# falownik.net
KiCad netlist of a schematic drawn in EAGLE
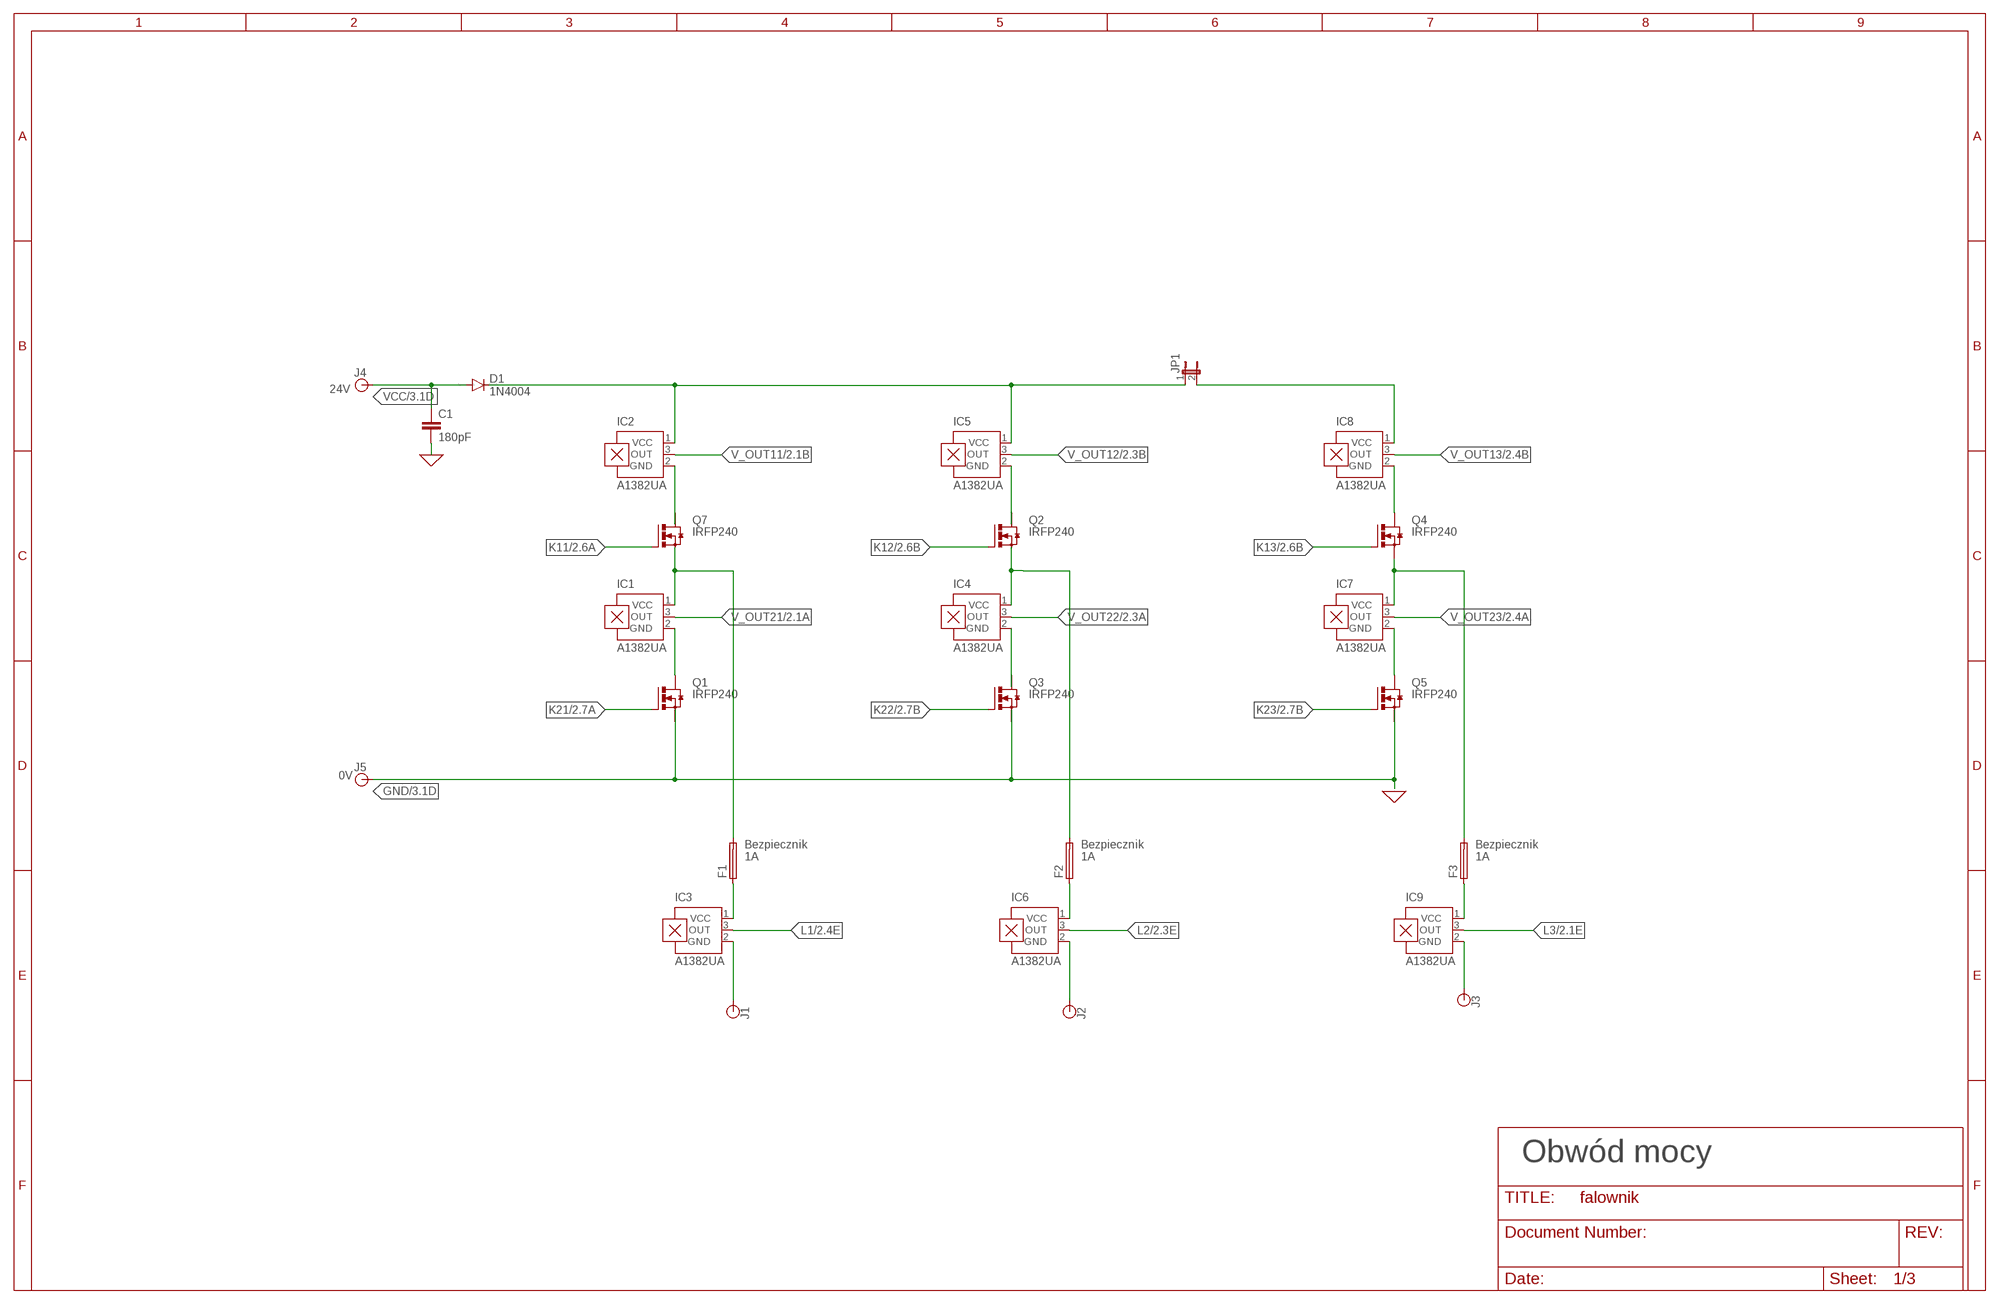
[diagram p0: schematic, sheet 1]
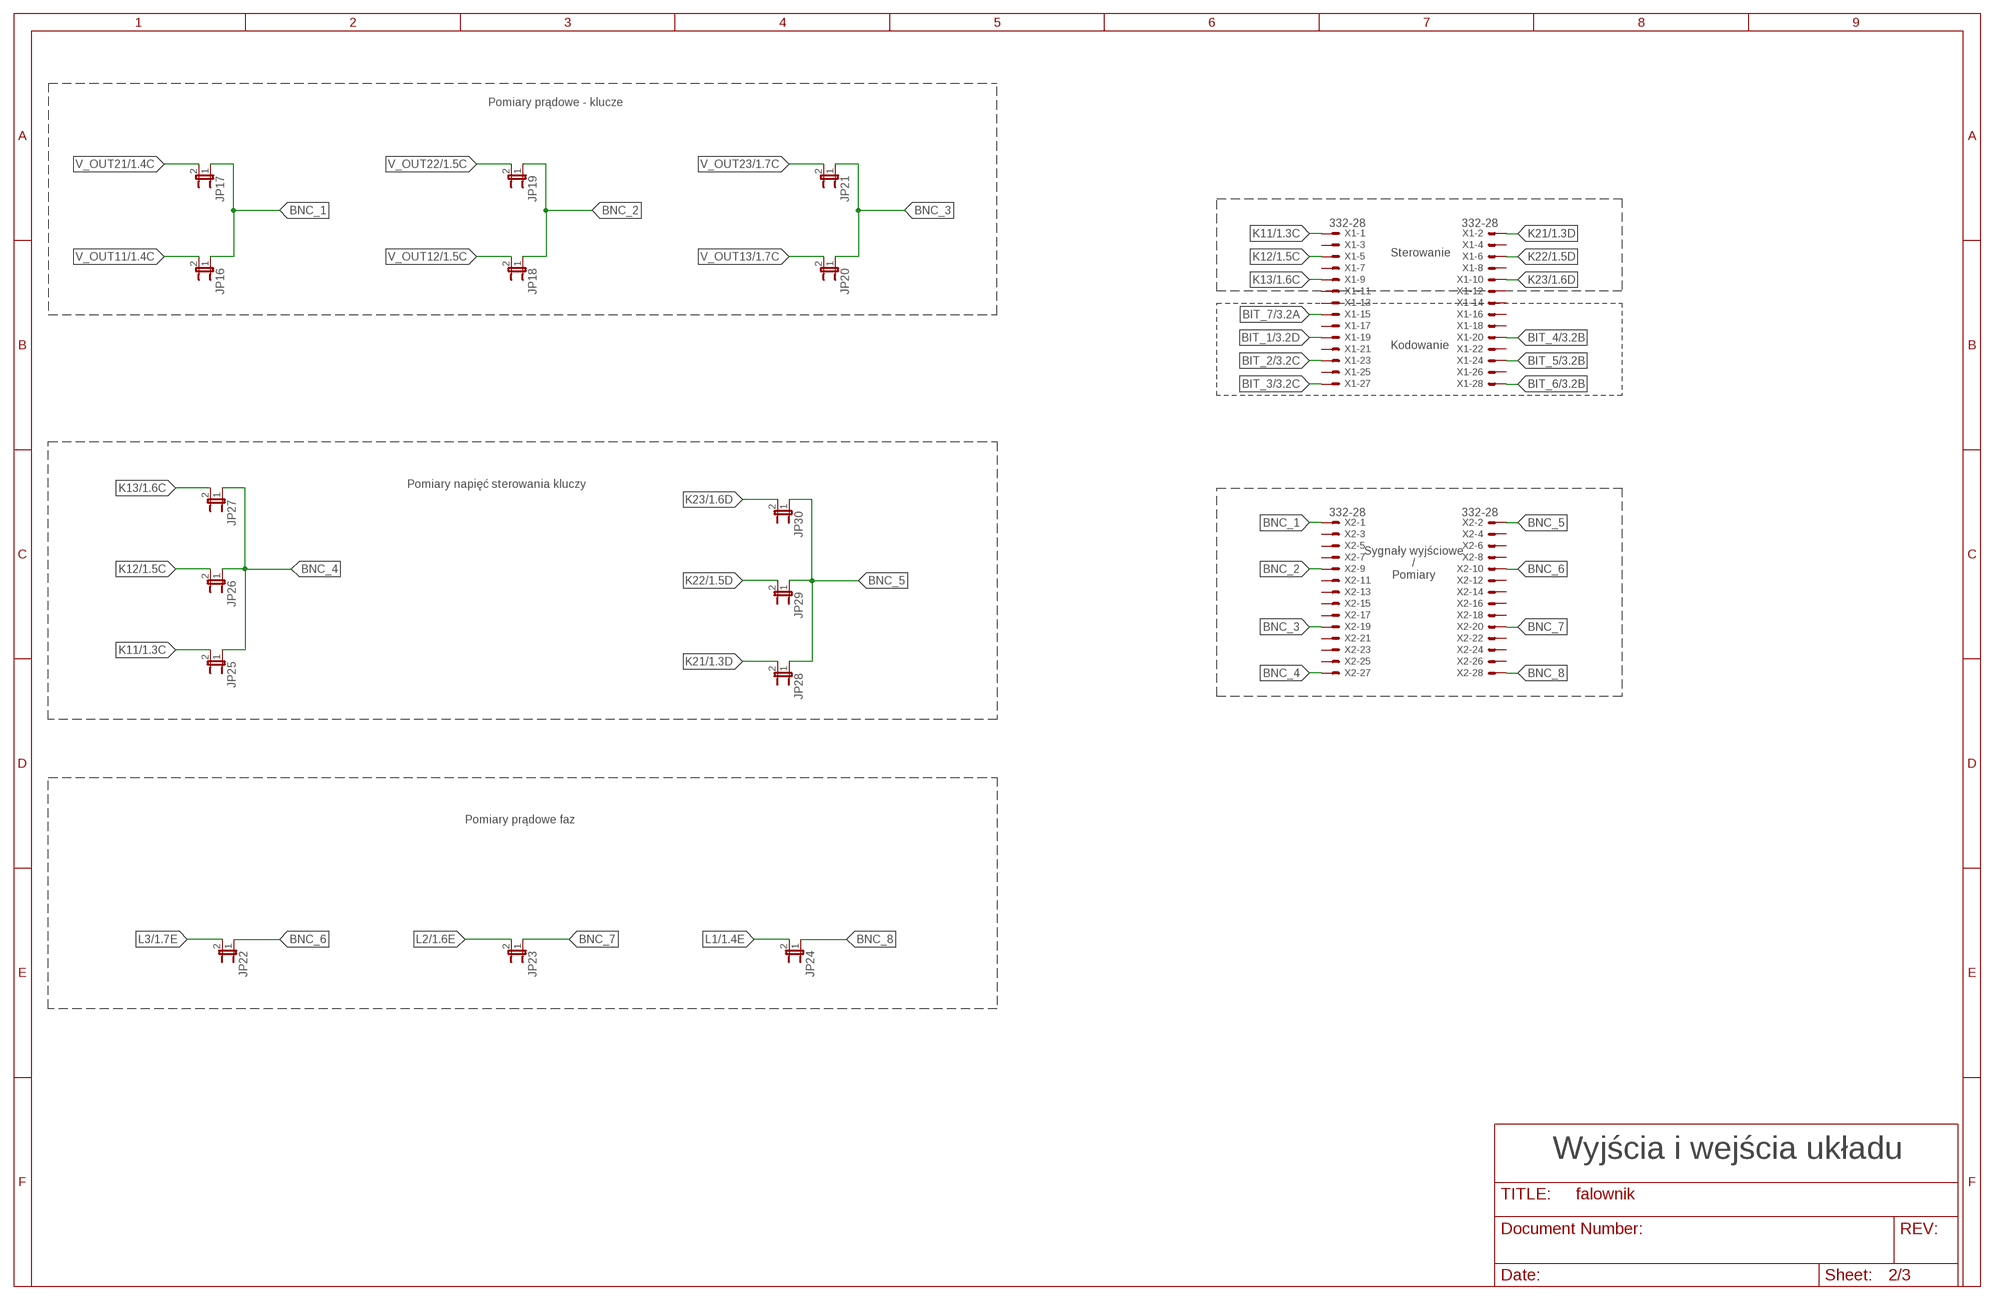
[diagram p1: schematic, sheet 2]
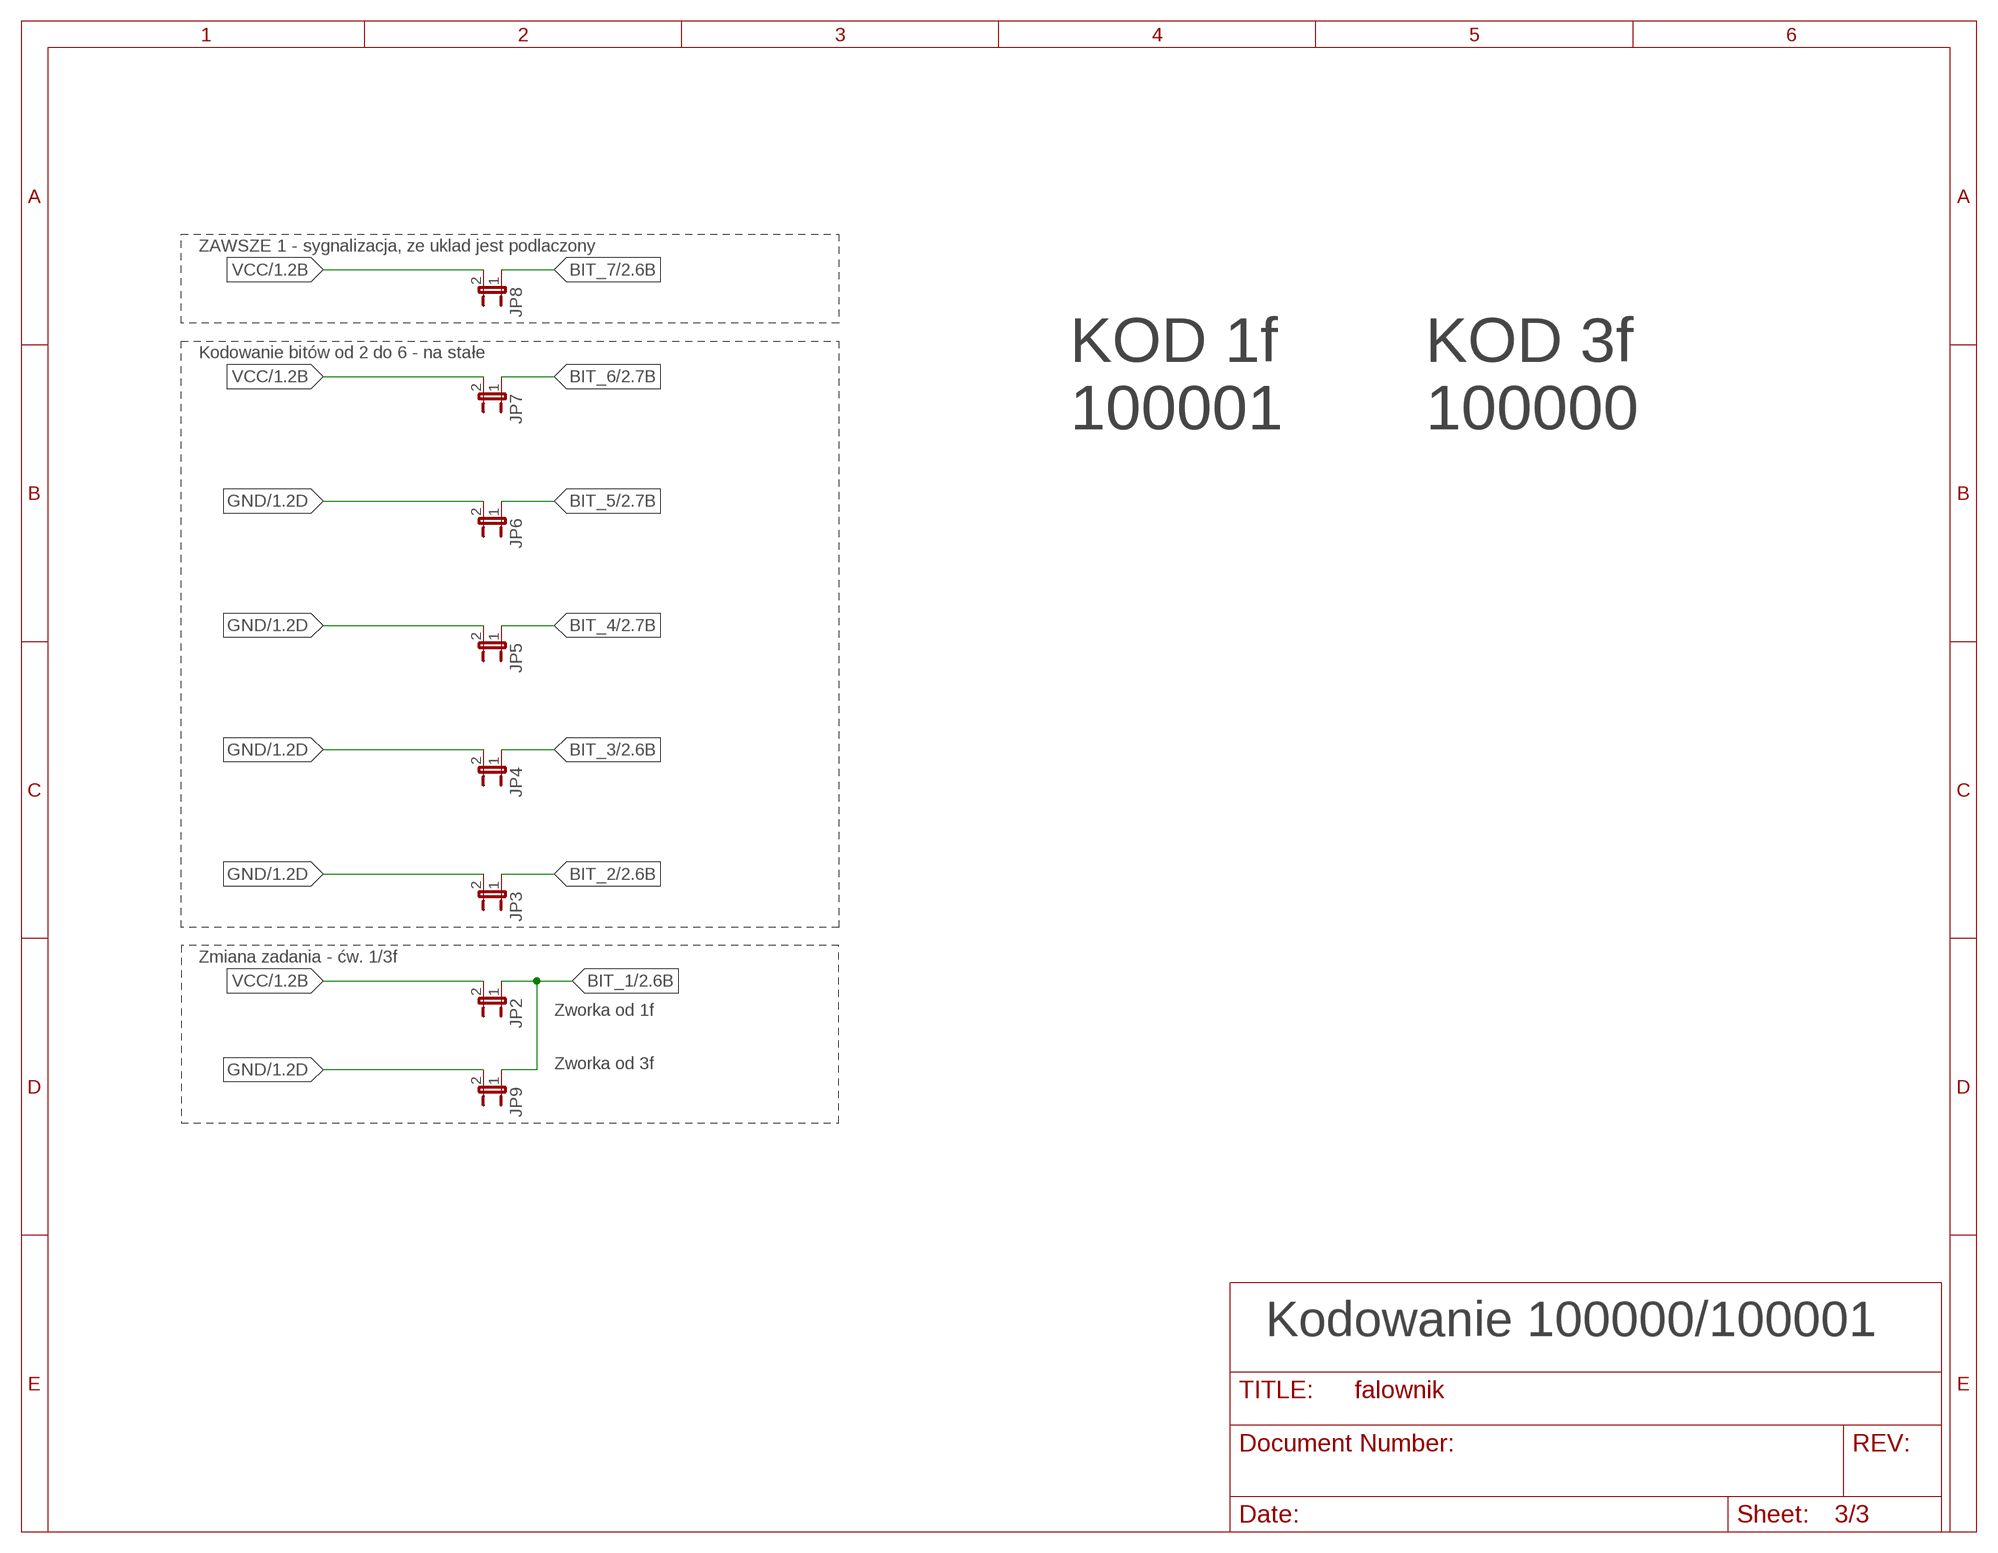
[diagram p2: schematic, sheet 3]

(export (version "E")
  (design (tool "Eeschema 10.0.6"))
  (components
    (comp (ref "C1")
      (value "180pF")
      (footprint "eagle-import:0603")
      (libsource (lib "eagle-import") (part "180PF-0603-50V-5%"))
    )
    (comp (ref "D1")
      (value "1N4004")
      (footprint "eagle-import:DO41-10")
      (libsource (lib "eagle-import") (part "1N4004"))
    )
    (comp (ref "F1")
      (value "GSH15")
      (footprint "eagle-import:GSH15")
      (fields (field (name "MPN") "64900001039"))
      (libsource (lib "eagle-import") (part "GSH15"))
    )
    (comp (ref "F2")
      (value "GSH15")
      (footprint "eagle-import:GSH15")
      (fields (field (name "MPN") "64900001039"))
      (libsource (lib "eagle-import") (part "GSH15"))
    )
    (comp (ref "F3")
      (value "GSH15")
      (footprint "eagle-import:GSH15")
      (fields (field (name "MPN") "64900001039"))
      (libsource (lib "eagle-import") (part "GSH15"))
    )
    (comp (ref "IC1")
      (value "A1382UA")
      (footprint "eagle-import:SIP3-UA")
      (fields (field (name "MPN") "A1382LUA-T"))
      (libsource (lib "eagle-import") (part "A13?UA82"))
    )
    (comp (ref "IC2")
      (value "A1382UA")
      (footprint "eagle-import:SIP3-UA")
      (fields (field (name "MPN") "A1382LUA-T"))
      (libsource (lib "eagle-import") (part "A13?UA82"))
    )
    (comp (ref "IC3")
      (value "A1382UA")
      (footprint "eagle-import:SIP3-UA")
      (fields (field (name "MPN") "A1382LUA-T"))
      (libsource (lib "eagle-import") (part "A13?UA82"))
    )
    (comp (ref "IC4")
      (value "A1382UA")
      (footprint "eagle-import:SIP3-UA")
      (fields (field (name "MPN") "A1382LUA-T"))
      (libsource (lib "eagle-import") (part "A13?UA82"))
    )
    (comp (ref "IC5")
      (value "A1382UA")
      (footprint "eagle-import:SIP3-UA")
      (fields (field (name "MPN") "A1382LUA-T"))
      (libsource (lib "eagle-import") (part "A13?UA82"))
    )
    (comp (ref "IC6")
      (value "A1382UA")
      (footprint "eagle-import:SIP3-UA")
      (fields (field (name "MPN") "A1382LUA-T"))
      (libsource (lib "eagle-import") (part "A13?UA82"))
    )
    (comp (ref "IC7")
      (value "A1382UA")
      (footprint "eagle-import:SIP3-UA")
      (fields (field (name "MPN") "A1382LUA-T"))
      (libsource (lib "eagle-import") (part "A13?UA82"))
    )
    (comp (ref "IC8")
      (value "A1382UA")
      (footprint "eagle-import:SIP3-UA")
      (fields (field (name "MPN") "A1382LUA-T"))
      (libsource (lib "eagle-import") (part "A13?UA82"))
    )
    (comp (ref "IC9")
      (value "A1382UA")
      (footprint "eagle-import:SIP3-UA")
      (fields (field (name "MPN") "A1382LUA-T"))
      (libsource (lib "eagle-import") (part "A13?UA82"))
    )
    (comp (ref "J1")
      (value "BANANA_CONN")
      (footprint "eagle-import:BANANA_CONN")
      (libsource (lib "eagle-import") (part "BANANA_CONN"))
    )
    (comp (ref "J2")
      (value "BANANA_CONN")
      (footprint "eagle-import:BANANA_CONN")
      (libsource (lib "eagle-import") (part "BANANA_CONN"))
    )
    (comp (ref "J3")
      (value "BANANA_CONN")
      (footprint "eagle-import:BANANA_CONN")
      (libsource (lib "eagle-import") (part "BANANA_CONN"))
    )
    (comp (ref "J4")
      (value "BANANA_CONN")
      (footprint "eagle-import:BANANA_CONN")
      (libsource (lib "eagle-import") (part "BANANA_CONN"))
    )
    (comp (ref "J5")
      (value "BANANA_CONN")
      (footprint "eagle-import:BANANA_CONN")
      (libsource (lib "eagle-import") (part "BANANA_CONN"))
    )
    (comp (ref "JP1")
      (value "JP1E")
      (footprint "eagle-import:JP1")
      (libsource (lib "eagle-import") (part "JP1E"))
    )
    (comp (ref "Q1")
      (value "IRFP240")
      (footprint "eagle-import:TO247BV")
      (libsource (lib "eagle-import") (part "IRFP240"))
    )
    (comp (ref "Q2")
      (value "IRFP240")
      (footprint "eagle-import:TO247BV")
      (libsource (lib "eagle-import") (part "IRFP240"))
    )
    (comp (ref "Q3")
      (value "IRFP240")
      (footprint "eagle-import:TO247BV")
      (libsource (lib "eagle-import") (part "IRFP240"))
    )
    (comp (ref "Q4")
      (value "IRFP240")
      (footprint "eagle-import:TO247BV")
      (libsource (lib "eagle-import") (part "IRFP240"))
    )
    (comp (ref "Q5")
      (value "IRFP240")
      (footprint "eagle-import:TO247BV")
      (libsource (lib "eagle-import") (part "IRFP240"))
    )
    (comp (ref "Q7")
      (value "IRFP240")
      (footprint "eagle-import:TO247BV")
      (libsource (lib "eagle-import") (part "IRFP240"))
    )
    (comp (ref "JP16")
      (value "JP1E")
      (footprint "eagle-import:JP1")
      (libsource (lib "eagle-import") (part "JP1E"))
    )
    (comp (ref "JP17")
      (value "JP1E")
      (footprint "eagle-import:JP1")
      (libsource (lib "eagle-import") (part "JP1E"))
    )
    (comp (ref "JP18")
      (value "JP1E")
      (footprint "eagle-import:JP1")
      (libsource (lib "eagle-import") (part "JP1E"))
    )
    (comp (ref "JP19")
      (value "JP1E")
      (footprint "eagle-import:JP1")
      (libsource (lib "eagle-import") (part "JP1E"))
    )
    (comp (ref "JP20")
      (value "JP1E")
      (footprint "eagle-import:JP1")
      (libsource (lib "eagle-import") (part "JP1E"))
    )
    (comp (ref "JP21")
      (value "JP1E")
      (footprint "eagle-import:JP1")
      (libsource (lib "eagle-import") (part "JP1E"))
    )
    (comp (ref "JP22")
      (value "JP1E")
      (footprint "eagle-import:JP1")
      (libsource (lib "eagle-import") (part "JP1E"))
    )
    (comp (ref "JP23")
      (value "JP1E")
      (footprint "eagle-import:JP1")
      (libsource (lib "eagle-import") (part "JP1E"))
    )
    (comp (ref "JP24")
      (value "JP1E")
      (footprint "eagle-import:JP1")
      (libsource (lib "eagle-import") (part "JP1E"))
    )
    (comp (ref "JP25")
      (value "JP1E")
      (footprint "eagle-import:JP1")
      (libsource (lib "eagle-import") (part "JP1E"))
    )
    (comp (ref "JP26")
      (value "JP1E")
      (footprint "eagle-import:JP1")
      (libsource (lib "eagle-import") (part "JP1E"))
    )
    (comp (ref "JP27")
      (value "JP1E")
      (footprint "eagle-import:JP1")
      (libsource (lib "eagle-import") (part "JP1E"))
    )
    (comp (ref "JP28")
      (value "JP1E")
      (footprint "eagle-import:JP1")
      (libsource (lib "eagle-import") (part "JP1E"))
    )
    (comp (ref "JP29")
      (value "JP1E")
      (footprint "eagle-import:JP1")
      (libsource (lib "eagle-import") (part "JP1E"))
    )
    (comp (ref "JP30")
      (value "JP1E")
      (footprint "eagle-import:JP1")
      (libsource (lib "eagle-import") (part "JP1E"))
    )
    (comp (ref "X1")
      (value "332-28")
      (footprint "eagle-import:332-28")
      (libsource (lib "eagle-import") (part "332-28"))
    )
    (comp (ref "X2")
      (value "332-28")
      (footprint "eagle-import:332-28")
      (libsource (lib "eagle-import") (part "332-28"))
    )
    (comp (ref "JP2")
      (value "JP1E")
      (footprint "eagle-import:JP1")
      (libsource (lib "eagle-import") (part "JP1E"))
    )
    (comp (ref "JP3")
      (value "JP1E")
      (footprint "eagle-import:JP1")
      (libsource (lib "eagle-import") (part "JP1E"))
    )
    (comp (ref "JP4")
      (value "JP1E")
      (footprint "eagle-import:JP1")
      (libsource (lib "eagle-import") (part "JP1E"))
    )
    (comp (ref "JP5")
      (value "JP1E")
      (footprint "eagle-import:JP1")
      (libsource (lib "eagle-import") (part "JP1E"))
    )
    (comp (ref "JP6")
      (value "JP1E")
      (footprint "eagle-import:JP1")
      (libsource (lib "eagle-import") (part "JP1E"))
    )
    (comp (ref "JP7")
      (value "JP1E")
      (footprint "eagle-import:JP1")
      (libsource (lib "eagle-import") (part "JP1E"))
    )
    (comp (ref "JP8")
      (value "JP1E")
      (footprint "eagle-import:JP1")
      (libsource (lib "eagle-import") (part "JP1E"))
    )
    (comp (ref "JP9")
      (value "JP1E")
      (footprint "eagle-import:JP1")
      (libsource (lib "eagle-import") (part "JP1E"))
    )
  )
  (nets
    (net (code "1") (name "BIT_1") (class "Default")
      (node (ref "JP2") (pin "1") (pinfunction "1_1") (pintype "passive"))
      (node (ref "JP9") (pin "1") (pinfunction "1_1") (pintype "passive"))
      (node (ref "X1") (pin "19") (pinfunction "S_19") (pintype "passive"))
    )
    (net (code "2") (name "BIT_2") (class "Default")
      (node (ref "JP3") (pin "1") (pinfunction "1_1") (pintype "passive"))
      (node (ref "X1") (pin "23") (pinfunction "S_23") (pintype "passive"))
    )
    (net (code "3") (name "BIT_3") (class "Default")
      (node (ref "JP4") (pin "1") (pinfunction "1_1") (pintype "passive"))
      (node (ref "X1") (pin "27") (pinfunction "S_27") (pintype "passive"))
    )
    (net (code "4") (name "BIT_4") (class "Default")
      (node (ref "JP5") (pin "1") (pinfunction "1_1") (pintype "passive"))
      (node (ref "X1") (pin "20") (pinfunction "S_20") (pintype "passive"))
    )
    (net (code "5") (name "BIT_5") (class "Default")
      (node (ref "JP6") (pin "1") (pinfunction "1_1") (pintype "passive"))
      (node (ref "X1") (pin "24") (pinfunction "S_24") (pintype "passive"))
    )
    (net (code "6") (name "BIT_6") (class "Default")
      (node (ref "JP7") (pin "1") (pinfunction "1_1") (pintype "passive"))
      (node (ref "X1") (pin "28") (pinfunction "S_28") (pintype "passive"))
    )
    (net (code "7") (name "BIT_7") (class "Default")
      (node (ref "JP8") (pin "1") (pinfunction "1_1") (pintype "passive"))
      (node (ref "X1") (pin "15") (pinfunction "S_15") (pintype "passive"))
    )
    (net (code "8") (name "BNC_1") (class "Default")
      (node (ref "JP16") (pin "1") (pinfunction "1_1") (pintype "passive"))
      (node (ref "JP17") (pin "1") (pinfunction "1_1") (pintype "passive"))
      (node (ref "X2") (pin "1") (pinfunction "S_1") (pintype "passive"))
    )
    (net (code "9") (name "BNC_2") (class "Default")
      (node (ref "JP18") (pin "1") (pinfunction "1_1") (pintype "passive"))
      (node (ref "JP19") (pin "1") (pinfunction "1_1") (pintype "passive"))
      (node (ref "X2") (pin "9") (pinfunction "S_9") (pintype "passive"))
    )
    (net (code "10") (name "BNC_3") (class "Default")
      (node (ref "JP20") (pin "1") (pinfunction "1_1") (pintype "passive"))
      (node (ref "JP21") (pin "1") (pinfunction "1_1") (pintype "passive"))
      (node (ref "X2") (pin "19") (pinfunction "S_19") (pintype "passive"))
    )
    (net (code "11") (name "BNC_4") (class "Default")
      (node (ref "JP25") (pin "1") (pinfunction "1_1") (pintype "passive"))
      (node (ref "JP26") (pin "1") (pinfunction "1_1") (pintype "passive"))
      (node (ref "JP27") (pin "1") (pinfunction "1_1") (pintype "passive"))
      (node (ref "X2") (pin "27") (pinfunction "S_27") (pintype "passive"))
    )
    (net (code "12") (name "BNC_5") (class "Default")
      (node (ref "JP28") (pin "1") (pinfunction "1_1") (pintype "passive"))
      (node (ref "JP29") (pin "1") (pinfunction "1_1") (pintype "passive"))
      (node (ref "JP30") (pin "1") (pinfunction "1_1") (pintype "passive"))
      (node (ref "X2") (pin "2") (pinfunction "S_2") (pintype "passive"))
    )
    (net (code "13") (name "BNC_6") (class "Default")
      (node (ref "JP22") (pin "1") (pinfunction "1_1") (pintype "passive"))
      (node (ref "X2") (pin "10") (pinfunction "S_10") (pintype "passive"))
    )
    (net (code "14") (name "BNC_7") (class "Default")
      (node (ref "JP23") (pin "1") (pinfunction "1_1") (pintype "passive"))
      (node (ref "X2") (pin "20") (pinfunction "S_20") (pintype "passive"))
    )
    (net (code "15") (name "BNC_8") (class "Default")
      (node (ref "JP24") (pin "1") (pinfunction "1_1") (pintype "passive"))
      (node (ref "X2") (pin "28") (pinfunction "S_28") (pintype "passive"))
    )
    (net (code "16") (name "GND") (class "Default")
      (node (ref "C1") (pin "2") (pinfunction "2_2") (pintype "passive"))
      (node (ref "J5") (pin "P$1") (pinfunction "1_P$1") (pintype "passive"))
      (node (ref "JP3") (pin "2") (pinfunction "2_2") (pintype "passive"))
      (node (ref "JP4") (pin "2") (pinfunction "2_2") (pintype "passive"))
      (node (ref "JP5") (pin "2") (pinfunction "2_2") (pintype "passive"))
      (node (ref "JP6") (pin "2") (pinfunction "2_2") (pintype "passive"))
      (node (ref "JP9") (pin "2") (pinfunction "2_2") (pintype "passive"))
      (node (ref "Q1") (pin "S") (pinfunction "S_S") (pintype "passive"))
      (node (ref "Q3") (pin "S") (pinfunction "S_S") (pintype "passive"))
      (node (ref "Q5") (pin "S") (pinfunction "S_S") (pintype "passive"))
    )
    (net (code "17") (name "K11") (class "Default")
      (node (ref "JP25") (pin "2") (pinfunction "2_2") (pintype "passive"))
      (node (ref "Q7") (pin "G") (pinfunction "G_G") (pintype "passive"))
      (node (ref "X1") (pin "1") (pinfunction "S_1") (pintype "passive"))
    )
    (net (code "18") (name "K12") (class "Default")
      (node (ref "JP26") (pin "2") (pinfunction "2_2") (pintype "passive"))
      (node (ref "Q2") (pin "G") (pinfunction "G_G") (pintype "passive"))
      (node (ref "X1") (pin "5") (pinfunction "S_5") (pintype "passive"))
    )
    (net (code "19") (name "K13") (class "Default")
      (node (ref "JP27") (pin "2") (pinfunction "2_2") (pintype "passive"))
      (node (ref "Q4") (pin "G") (pinfunction "G_G") (pintype "passive"))
      (node (ref "X1") (pin "9") (pinfunction "S_9") (pintype "passive"))
    )
    (net (code "20") (name "K21") (class "Default")
      (node (ref "JP28") (pin "2") (pinfunction "2_2") (pintype "passive"))
      (node (ref "Q1") (pin "G") (pinfunction "G_G") (pintype "passive"))
      (node (ref "X1") (pin "2") (pinfunction "S_2") (pintype "passive"))
    )
    (net (code "21") (name "K22") (class "Default")
      (node (ref "JP29") (pin "2") (pinfunction "2_2") (pintype "passive"))
      (node (ref "Q3") (pin "G") (pinfunction "G_G") (pintype "passive"))
      (node (ref "X1") (pin "6") (pinfunction "S_6") (pintype "passive"))
    )
    (net (code "22") (name "K23") (class "Default")
      (node (ref "JP30") (pin "2") (pinfunction "2_2") (pintype "passive"))
      (node (ref "Q5") (pin "G") (pinfunction "G_G") (pintype "passive"))
      (node (ref "X1") (pin "10") (pinfunction "S_10") (pintype "passive"))
    )
    (net (code "23") (name "L1") (class "Default")
      (node (ref "IC3") (pin "3") (pinfunction "OUT_3") (pintype "output"))
      (node (ref "JP24") (pin "2") (pinfunction "2_2") (pintype "passive"))
    )
    (net (code "24") (name "L2") (class "Default")
      (node (ref "IC6") (pin "3") (pinfunction "OUT_3") (pintype "output"))
      (node (ref "JP23") (pin "2") (pinfunction "2_2") (pintype "passive"))
    )
    (net (code "25") (name "L3") (class "Default")
      (node (ref "IC9") (pin "3") (pinfunction "OUT_3") (pintype "output"))
      (node (ref "JP22") (pin "2") (pinfunction "2_2") (pintype "passive"))
    )
    (net (code "26") (name "Net-(IC1-GND)") (class "Default")
      (node (ref "IC1") (pin "2") (pinfunction "GND_2") (pintype "power_in"))
      (node (ref "Q1") (pin "D") (pinfunction "D_D") (pintype "passive"))
    )
    (net (code "27") (name "Net-(IC1-VCC)") (class "Default")
      (node (ref "F1") (pin "2") (pinfunction "2_2") (pintype "passive"))
      (node (ref "IC1") (pin "1") (pinfunction "VCC_1") (pintype "power_in"))
      (node (ref "Q7") (pin "S") (pinfunction "S_S") (pintype "passive"))
    )
    (net (code "28") (name "Net-(IC2-GND)") (class "Default")
      (node (ref "IC2") (pin "2") (pinfunction "GND_2") (pintype "power_in"))
      (node (ref "Q7") (pin "D") (pinfunction "D_D") (pintype "passive"))
    )
    (net (code "29") (name "Net-(IC2-VCC)") (class "Default")
      (node (ref "D1") (pin "C") (pinfunction "C_C") (pintype "passive"))
      (node (ref "IC2") (pin "1") (pinfunction "VCC_1") (pintype "power_in"))
      (node (ref "IC5") (pin "1") (pinfunction "VCC_1") (pintype "power_in"))
      (node (ref "JP1") (pin "1") (pinfunction "1_1") (pintype "passive"))
    )
    (net (code "30") (name "Net-(IC3-GND)") (class "Default")
      (node (ref "IC3") (pin "2") (pinfunction "GND_2") (pintype "power_in"))
      (node (ref "J1") (pin "P$1") (pinfunction "1_P$1") (pintype "passive"))
    )
    (net (code "31") (name "Net-(IC3-VCC)") (class "Default")
      (node (ref "F1") (pin "1") (pinfunction "1_1") (pintype "passive"))
      (node (ref "IC3") (pin "1") (pinfunction "VCC_1") (pintype "power_in"))
    )
    (net (code "32") (name "Net-(IC4-GND)") (class "Default")
      (node (ref "IC4") (pin "2") (pinfunction "GND_2") (pintype "power_in"))
      (node (ref "Q3") (pin "D") (pinfunction "D_D") (pintype "passive"))
    )
    (net (code "33") (name "Net-(IC4-VCC)") (class "Default")
      (node (ref "F2") (pin "2") (pinfunction "2_2") (pintype "passive"))
      (node (ref "IC4") (pin "1") (pinfunction "VCC_1") (pintype "power_in"))
      (node (ref "Q2") (pin "S") (pinfunction "S_S") (pintype "passive"))
    )
    (net (code "34") (name "Net-(IC5-GND)") (class "Default")
      (node (ref "IC5") (pin "2") (pinfunction "GND_2") (pintype "power_in"))
      (node (ref "Q2") (pin "D") (pinfunction "D_D") (pintype "passive"))
    )
    (net (code "35") (name "Net-(IC6-GND)") (class "Default")
      (node (ref "IC6") (pin "2") (pinfunction "GND_2") (pintype "power_in"))
      (node (ref "J2") (pin "P$1") (pinfunction "1_P$1") (pintype "passive"))
    )
    (net (code "36") (name "Net-(IC6-VCC)") (class "Default")
      (node (ref "F2") (pin "1") (pinfunction "1_1") (pintype "passive"))
      (node (ref "IC6") (pin "1") (pinfunction "VCC_1") (pintype "power_in"))
    )
    (net (code "37") (name "Net-(IC7-GND)") (class "Default")
      (node (ref "IC7") (pin "2") (pinfunction "GND_2") (pintype "power_in"))
      (node (ref "Q5") (pin "D") (pinfunction "D_D") (pintype "passive"))
    )
    (net (code "38") (name "Net-(IC7-VCC)") (class "Default")
      (node (ref "F3") (pin "2") (pinfunction "2_2") (pintype "passive"))
      (node (ref "IC7") (pin "1") (pinfunction "VCC_1") (pintype "power_in"))
      (node (ref "Q4") (pin "S") (pinfunction "S_S") (pintype "passive"))
    )
    (net (code "39") (name "Net-(IC8-GND)") (class "Default")
      (node (ref "IC8") (pin "2") (pinfunction "GND_2") (pintype "power_in"))
      (node (ref "Q4") (pin "D") (pinfunction "D_D") (pintype "passive"))
    )
    (net (code "40") (name "Net-(IC8-VCC)") (class "Default")
      (node (ref "IC8") (pin "1") (pinfunction "VCC_1") (pintype "power_in"))
      (node (ref "JP1") (pin "2") (pinfunction "2_2") (pintype "passive"))
    )
    (net (code "41") (name "Net-(IC9-GND)") (class "Default")
      (node (ref "IC9") (pin "2") (pinfunction "GND_2") (pintype "power_in"))
      (node (ref "J3") (pin "P$1") (pinfunction "1_P$1") (pintype "passive"))
    )
    (net (code "42") (name "Net-(IC9-VCC)") (class "Default")
      (node (ref "F3") (pin "1") (pinfunction "1_1") (pintype "passive"))
      (node (ref "IC9") (pin "1") (pinfunction "VCC_1") (pintype "power_in"))
    )
    (net (code "43") (name "VCC") (class "Default")
      (node (ref "C1") (pin "1") (pinfunction "1_1") (pintype "passive"))
      (node (ref "D1") (pin "A") (pinfunction "A_A") (pintype "passive"))
      (node (ref "J4") (pin "P$1") (pinfunction "1_P$1") (pintype "passive"))
      (node (ref "JP2") (pin "2") (pinfunction "2_2") (pintype "passive"))
      (node (ref "JP7") (pin "2") (pinfunction "2_2") (pintype "passive"))
      (node (ref "JP8") (pin "2") (pinfunction "2_2") (pintype "passive"))
    )
    (net (code "44") (name "V_OUT11") (class "Default")
      (node (ref "IC2") (pin "3") (pinfunction "OUT_3") (pintype "output"))
      (node (ref "JP16") (pin "2") (pinfunction "2_2") (pintype "passive"))
    )
    (net (code "45") (name "V_OUT12") (class "Default")
      (node (ref "IC5") (pin "3") (pinfunction "OUT_3") (pintype "output"))
      (node (ref "JP18") (pin "2") (pinfunction "2_2") (pintype "passive"))
    )
    (net (code "46") (name "V_OUT13") (class "Default")
      (node (ref "IC8") (pin "3") (pinfunction "OUT_3") (pintype "output"))
      (node (ref "JP20") (pin "2") (pinfunction "2_2") (pintype "passive"))
    )
    (net (code "47") (name "V_OUT21") (class "Default")
      (node (ref "IC1") (pin "3") (pinfunction "OUT_3") (pintype "output"))
      (node (ref "JP17") (pin "2") (pinfunction "2_2") (pintype "passive"))
    )
    (net (code "48") (name "V_OUT22") (class "Default")
      (node (ref "IC4") (pin "3") (pinfunction "OUT_3") (pintype "output"))
      (node (ref "JP19") (pin "2") (pinfunction "2_2") (pintype "passive"))
    )
    (net (code "49") (name "V_OUT23") (class "Default")
      (node (ref "IC7") (pin "3") (pinfunction "OUT_3") (pintype "output"))
      (node (ref "JP21") (pin "2") (pinfunction "2_2") (pintype "passive"))
    )
    (net (code "50") (name "unconnected-(X1AA-S-Pad8)") (class "Default")
      (node (ref "X1") (pin "8") (pinfunction "S_8") (pintype "passive"))
    )
    (net (code "51") (name "unconnected-(X1C-S-Pad11)") (class "Default")
      (node (ref "X1") (pin "11") (pinfunction "S_11") (pintype "passive"))
    )
    (net (code "52") (name "unconnected-(X1D-S-Pad12)") (class "Default")
      (node (ref "X1") (pin "12") (pinfunction "S_12") (pintype "passive"))
    )
    (net (code "53") (name "unconnected-(X1E-S-Pad13)") (class "Default")
      (node (ref "X1") (pin "13") (pinfunction "S_13") (pintype "passive"))
    )
    (net (code "54") (name "unconnected-(X1F-S-Pad14)") (class "Default")
      (node (ref "X1") (pin "14") (pinfunction "S_14") (pintype "passive"))
    )
    (net (code "55") (name "unconnected-(X1H-S-Pad16)") (class "Default")
      (node (ref "X1") (pin "16") (pinfunction "S_16") (pintype "passive"))
    )
    (net (code "56") (name "unconnected-(X1I-S-Pad17)") (class "Default")
      (node (ref "X1") (pin "17") (pinfunction "S_17") (pintype "passive"))
    )
    (net (code "57") (name "unconnected-(X1J-S-Pad18)") (class "Default")
      (node (ref "X1") (pin "18") (pinfunction "S_18") (pintype "passive"))
    )
    (net (code "58") (name "unconnected-(X1N-S-Pad21)") (class "Default")
      (node (ref "X1") (pin "21") (pinfunction "S_21") (pintype "passive"))
    )
    (net (code "59") (name "unconnected-(X1O-S-Pad22)") (class "Default")
      (node (ref "X1") (pin "22") (pinfunction "S_22") (pintype "passive"))
    )
    (net (code "60") (name "unconnected-(X1R-S-Pad25)") (class "Default")
      (node (ref "X1") (pin "25") (pinfunction "S_25") (pintype "passive"))
    )
    (net (code "61") (name "unconnected-(X1S-S-Pad26)") (class "Default")
      (node (ref "X1") (pin "26") (pinfunction "S_26") (pintype "passive"))
    )
    (net (code "62") (name "unconnected-(X1V-S-Pad3)") (class "Default")
      (node (ref "X1") (pin "3") (pinfunction "S_3") (pintype "passive"))
    )
    (net (code "63") (name "unconnected-(X1W-S-Pad4)") (class "Default")
      (node (ref "X1") (pin "4") (pinfunction "S_4") (pintype "passive"))
    )
    (net (code "64") (name "unconnected-(X1Z-S-Pad7)") (class "Default")
      (node (ref "X1") (pin "7") (pinfunction "S_7") (pintype "passive"))
    )
    (net (code "65") (name "unconnected-(X2AA-S-Pad8)") (class "Default")
      (node (ref "X2") (pin "8") (pinfunction "S_8") (pintype "passive"))
    )
    (net (code "66") (name "unconnected-(X2C-S-Pad11)") (class "Default")
      (node (ref "X2") (pin "11") (pinfunction "S_11") (pintype "passive"))
    )
    (net (code "67") (name "unconnected-(X2D-S-Pad12)") (class "Default")
      (node (ref "X2") (pin "12") (pinfunction "S_12") (pintype "passive"))
    )
    (net (code "68") (name "unconnected-(X2E-S-Pad13)") (class "Default")
      (node (ref "X2") (pin "13") (pinfunction "S_13") (pintype "passive"))
    )
    (net (code "69") (name "unconnected-(X2F-S-Pad14)") (class "Default")
      (node (ref "X2") (pin "14") (pinfunction "S_14") (pintype "passive"))
    )
    (net (code "70") (name "unconnected-(X2G-S-Pad15)") (class "Default")
      (node (ref "X2") (pin "15") (pinfunction "S_15") (pintype "passive"))
    )
    (net (code "71") (name "unconnected-(X2H-S-Pad16)") (class "Default")
      (node (ref "X2") (pin "16") (pinfunction "S_16") (pintype "passive"))
    )
    (net (code "72") (name "unconnected-(X2I-S-Pad17)") (class "Default")
      (node (ref "X2") (pin "17") (pinfunction "S_17") (pintype "passive"))
    )
    (net (code "73") (name "unconnected-(X2J-S-Pad18)") (class "Default")
      (node (ref "X2") (pin "18") (pinfunction "S_18") (pintype "passive"))
    )
    (net (code "74") (name "unconnected-(X2N-S-Pad21)") (class "Default")
      (node (ref "X2") (pin "21") (pinfunction "S_21") (pintype "passive"))
    )
    (net (code "75") (name "unconnected-(X2O-S-Pad22)") (class "Default")
      (node (ref "X2") (pin "22") (pinfunction "S_22") (pintype "passive"))
    )
    (net (code "76") (name "unconnected-(X2P-S-Pad23)") (class "Default")
      (node (ref "X2") (pin "23") (pinfunction "S_23") (pintype "passive"))
    )
    (net (code "77") (name "unconnected-(X2Q-S-Pad24)") (class "Default")
      (node (ref "X2") (pin "24") (pinfunction "S_24") (pintype "passive"))
    )
    (net (code "78") (name "unconnected-(X2R-S-Pad25)") (class "Default")
      (node (ref "X2") (pin "25") (pinfunction "S_25") (pintype "passive"))
    )
    (net (code "79") (name "unconnected-(X2S-S-Pad26)") (class "Default")
      (node (ref "X2") (pin "26") (pinfunction "S_26") (pintype "passive"))
    )
    (net (code "80") (name "unconnected-(X2V-S-Pad3)") (class "Default")
      (node (ref "X2") (pin "3") (pinfunction "S_3") (pintype "passive"))
    )
    (net (code "81") (name "unconnected-(X2W-S-Pad4)") (class "Default")
      (node (ref "X2") (pin "4") (pinfunction "S_4") (pintype "passive"))
    )
    (net (code "82") (name "unconnected-(X2X-S-Pad5)") (class "Default")
      (node (ref "X2") (pin "5") (pinfunction "S_5") (pintype "passive"))
    )
    (net (code "83") (name "unconnected-(X2Y-S-Pad6)") (class "Default")
      (node (ref "X2") (pin "6") (pinfunction "S_6") (pintype "passive"))
    )
    (net (code "84") (name "unconnected-(X2Z-S-Pad7)") (class "Default")
      (node (ref "X2") (pin "7") (pinfunction "S_7") (pintype "passive"))
    )
  )
)
